# MagicDice_v1_2.net
KiCad netlist of a schematic drawn in EAGLE
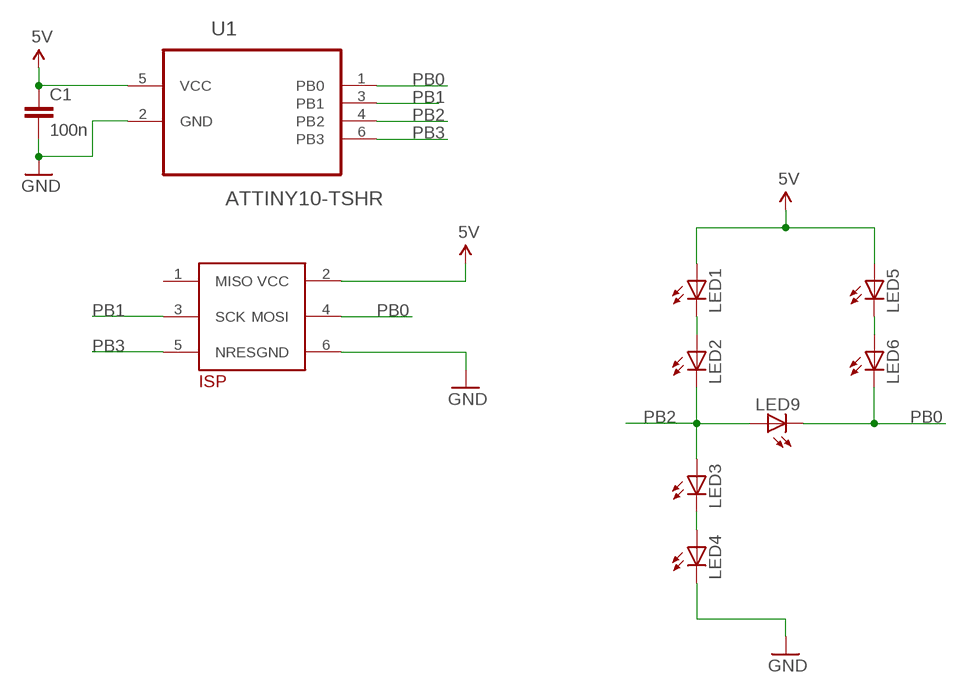
[diagram p0: schematic, sheet 1]

(export (version "E")
  (design (tool "Eeschema 10.0.6"))
  (components
    (comp (ref "C1")
      (value "100n")
      (footprint "eagle-import:0805")
      (libsource (lib "eagle-import") (part "CAP0805"))
    )
    (comp (ref "LED1")
      (value "LED0603")
      (footprint "eagle-import:LED-0603")
      (libsource (lib "eagle-import") (part "LED0603"))
    )
    (comp (ref "LED2")
      (value "LED0603")
      (footprint "eagle-import:LED-0603")
      (libsource (lib "eagle-import") (part "LED0603"))
    )
    (comp (ref "LED3")
      (value "LED0603")
      (footprint "eagle-import:LED-0603")
      (libsource (lib "eagle-import") (part "LED0603"))
    )
    (comp (ref "LED4")
      (value "LED0603")
      (footprint "eagle-import:LED-0603")
      (libsource (lib "eagle-import") (part "LED0603"))
    )
    (comp (ref "LED5")
      (value "LED0603")
      (footprint "eagle-import:LED-0603")
      (libsource (lib "eagle-import") (part "LED0603"))
    )
    (comp (ref "LED6")
      (value "LED0603")
      (footprint "eagle-import:LED-0603")
      (libsource (lib "eagle-import") (part "LED0603"))
    )
    (comp (ref "LED9")
      (value "LED0603")
      (footprint "eagle-import:LED-0603")
      (libsource (lib "eagle-import") (part "LED0603"))
    )
    (comp (ref "U$1")
      (value "TB_ISPEDGE_2X3")
      (footprint "eagle-import:ISP_EDGE2X3")
      (libsource (lib "eagle-import") (part "TB_ISPEDGE_2X3"))
    )
    (comp (ref "U1")
      (value "ATTINY10-TSHR")
      (footprint "eagle-import:SOT95P280X145-6N")
      (libsource (lib "eagle-import") (part "ATTINY10-TSHR"))
    )
  )
  (nets
    (net (code "1") (name "/PB0") (class "Default")
      (node (ref "LED6") (pin "C") (pinfunction "C_C") (pintype "passive"))
      (node (ref "LED9") (pin "C") (pinfunction "C_C") (pintype "passive"))
      (node (ref "U$1") (pin "4") (pinfunction "MOSI_4") (pintype "bidirectional"))
      (node (ref "U1") (pin "1") (pinfunction "PB0_1") (pintype "bidirectional"))
    )
    (net (code "2") (name "/PB1") (class "Default")
      (node (ref "U$1") (pin "3") (pinfunction "SCK_3") (pintype "bidirectional"))
      (node (ref "U1") (pin "3") (pinfunction "PB1_3") (pintype "bidirectional"))
    )
    (net (code "3") (name "/PB2") (class "Default")
      (node (ref "LED2") (pin "C") (pinfunction "C_C") (pintype "passive"))
      (node (ref "LED3") (pin "A") (pinfunction "A_A") (pintype "passive"))
      (node (ref "LED9") (pin "A") (pinfunction "A_A") (pintype "passive"))
      (node (ref "U1") (pin "4") (pinfunction "PB2_4") (pintype "bidirectional"))
    )
    (net (code "4") (name "/PB3") (class "Default")
      (node (ref "U$1") (pin "5") (pinfunction "NRES_5") (pintype "bidirectional"))
      (node (ref "U1") (pin "6") (pinfunction "PB3_6") (pintype "bidirectional"))
    )
    (net (code "5") (name "5V") (class "Default")
      (node (ref "C1") (pin "1") (pinfunction "1_1") (pintype "passive"))
      (node (ref "LED1") (pin "A") (pinfunction "A_A") (pintype "passive"))
      (node (ref "LED5") (pin "A") (pinfunction "A_A") (pintype "passive"))
      (node (ref "U$1") (pin "2") (pinfunction "VCC_2") (pintype "bidirectional"))
      (node (ref "U1") (pin "5") (pinfunction "VCC_5") (pintype "power_in"))
    )
    (net (code "6") (name "GND") (class "Default")
      (node (ref "C1") (pin "2") (pinfunction "2_2") (pintype "passive"))
      (node (ref "LED4") (pin "C") (pinfunction "C_C") (pintype "passive"))
      (node (ref "U$1") (pin "6") (pinfunction "GND_6") (pintype "bidirectional"))
      (node (ref "U1") (pin "2") (pinfunction "GND_2") (pintype "passive"))
    )
    (net (code "7") (name "Net-(LED1-PadC)") (class "Default")
      (node (ref "LED1") (pin "C") (pinfunction "C_C") (pintype "passive"))
      (node (ref "LED2") (pin "A") (pinfunction "A_A") (pintype "passive"))
    )
    (net (code "8") (name "Net-(LED3-PadC)") (class "Default")
      (node (ref "LED3") (pin "C") (pinfunction "C_C") (pintype "passive"))
      (node (ref "LED4") (pin "A") (pinfunction "A_A") (pintype "passive"))
    )
    (net (code "9") (name "Net-(LED5-PadC)") (class "Default")
      (node (ref "LED5") (pin "C") (pinfunction "C_C") (pintype "passive"))
      (node (ref "LED6") (pin "A") (pinfunction "A_A") (pintype "passive"))
    )
    (net (code "10") (name "unconnected-(U$1-MISO-Pad1)") (class "Default")
      (node (ref "U$1") (pin "1") (pinfunction "MISO_1") (pintype "bidirectional"))
    )
  )
)
